# NewDoor.net
KiCad netlist of a schematic drawn in EAGLE
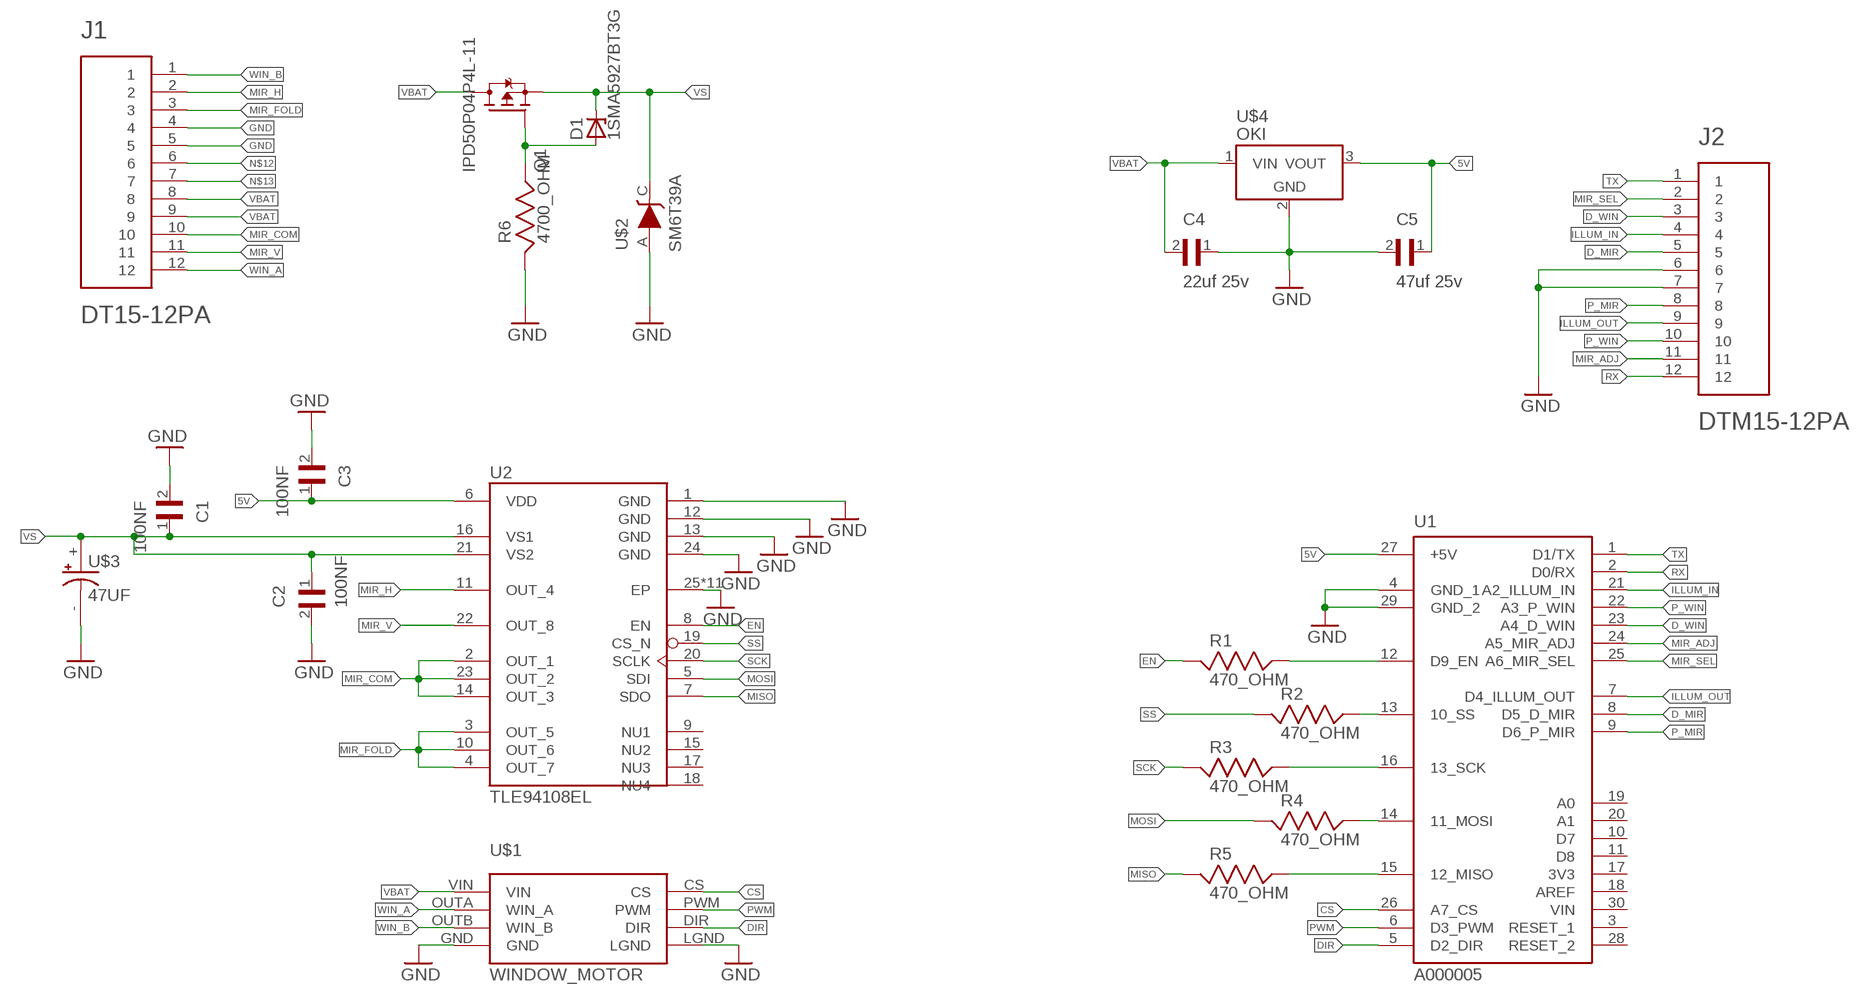
[diagram p0: schematic, sheet 1]

(export (version "E")
  (design (tool "Eeschema 10.0.6"))
  (components
    (comp (ref "C1")
      (value "100NF")
      (footprint "eagle-import:CAPC3216X110N")
      (fields (field (name "MF") "KEMET") (field (name "MP") "C1206C104J5RACTU"))
      (libsource (lib "eagle-import") (part "100NF"))
    )
    (comp (ref "C2")
      (value "100NF")
      (footprint "eagle-import:CAPC3216X110N")
      (fields (field (name "MF") "KEMET") (field (name "MP") "C1206C104J5RACTU"))
      (libsource (lib "eagle-import") (part "100NF"))
    )
    (comp (ref "C3")
      (value "100NF")
      (footprint "eagle-import:CAPC3216X110N")
      (fields (field (name "MF") "KEMET") (field (name "MP") "C1206C104J5RACTU"))
      (libsource (lib "eagle-import") (part "100NF"))
    )
    (comp (ref "C4")
      (value "22uf 25v")
      (footprint "eagle-import:CAP3216X125N")
      (fields (field (name "MF") "Murata Electronics") (field (name "MP") "GRM31CC81E226KE11L"))
      (libsource (lib "eagle-import") (part "GRM31CC81E226KE11L"))
    )
    (comp (ref "C5")
      (value "47uf 25v")
      (footprint "eagle-import:CAP3216X125N")
      (fields (field (name "MF") "Murata Electronics") (field (name "MP") "GRM31CC81E226KE11L"))
      (libsource (lib "eagle-import") (part "GRM31CC81E226KE11L"))
    )
    (comp (ref "D1")
      (value "1SMA5927BT3G")
      (footprint "eagle-import:DO214AC")
      (fields (field (name "MF") "ON Semiconductor"))
      (libsource (lib "eagle-import") (part "1SMA59BT3G27"))
    )
    (comp (ref "J1")
      (value "DT15-12PA")
      (footprint "eagle-import:TE_DT15-12PA")
      (fields (field (name "MF") "TE Connectivity"))
      (libsource (lib "eagle-import") (part "DT15-12PA"))
    )
    (comp (ref "J2")
      (value "DTM15-12PA")
      (footprint "eagle-import:TE_DTM15-12PA")
      (fields (field (name "MF") "TE Connectivity") (field (name "MPN") "DTM15-12PA "))
      (libsource (lib "eagle-import") (part "DTM15-12PA"))
    )
    (comp (ref "Q1")
      (value "IPD50P04P4L-11")
      (footprint "eagle-import:DPAK228P998X235-3N")
      (fields (field (name "MF") "Infineon Technologies"))
      (libsource (lib "eagle-import") (part "IPD50P04P4L-11"))
    )
    (comp (ref "R1")
      (value "470_OHM")
      (footprint "eagle-import:RESC3216X65")
      (fields (field (name "MF") "Yageo") (field (name "MP") "RC1206FR-13470RL"))
      (libsource (lib "eagle-import") (part "470_OHM"))
    )
    (comp (ref "R2")
      (value "470_OHM")
      (footprint "eagle-import:RESC3216X65")
      (fields (field (name "MF") "Yageo") (field (name "MP") "RC1206FR-13470RL"))
      (libsource (lib "eagle-import") (part "470_OHM"))
    )
    (comp (ref "R3")
      (value "470_OHM")
      (footprint "eagle-import:RESC3216X65")
      (fields (field (name "MF") "Yageo") (field (name "MP") "RC1206FR-13470RL"))
      (libsource (lib "eagle-import") (part "470_OHM"))
    )
    (comp (ref "R4")
      (value "470_OHM")
      (footprint "eagle-import:RESC3216X65")
      (fields (field (name "MF") "Yageo") (field (name "MP") "RC1206FR-13470RL"))
      (libsource (lib "eagle-import") (part "470_OHM"))
    )
    (comp (ref "R5")
      (value "470_OHM")
      (footprint "eagle-import:RESC3216X65")
      (fields (field (name "MF") "Yageo") (field (name "MP") "RC1206FR-13470RL"))
      (libsource (lib "eagle-import") (part "470_OHM"))
    )
    (comp (ref "R6")
      (value "4700_OHM")
      (footprint "eagle-import:RESC3216X70")
      (fields (field (name "MF") "Panasonic Electronic") (field (name "MP") "ERJ-8ENF4701V"))
      (libsource (lib "eagle-import") (part "4700_OHM"))
    )
    (comp (ref "U$1")
      (value "WINDOW_MOTOR")
      (footprint "eagle-import:POLOLU")
      (libsource (lib "eagle-import") (part "WINDOW_MOTOR"))
    )
    (comp (ref "U$2")
      (value "SM6T39A")
      (footprint "eagle-import:SM6T39A")
      (libsource (lib "eagle-import") (part "SM6T39A"))
    )
    (comp (ref "U$3")
      (value "47UF")
      (footprint "eagle-import:CAPAE1030X1200")
      (fields (field (name "MF") "Panasonic") (field (name "MP") "EEE-FC1C471AP"))
      (libsource (lib "eagle-import") (part "47UF"))
    )
    (comp (ref "U$4")
      (value "OKI")
      (footprint "eagle-import:OKI-78SR-H")
      (libsource (lib "eagle-import") (part "OKI"))
    )
    (comp (ref "U1")
      (value "A000005")
      (footprint "eagle-import:ARDUINO_A000005")
      (fields (field (name "MF") "Arduino"))
      (libsource (lib "eagle-import") (part "A000005"))
    )
    (comp (ref "U2")
      (value "TLE94108EL")
      (footprint "eagle-import:SOP65P600X170-25N")
      (libsource (lib "eagle-import") (part "TLE94108EL"))
    )
  )
  (nets
    (net (code "1") (name "5V") (class "Default")
      (node (ref "C3") (pin "1") (pinfunction "1_1") (pintype "passive"))
      (node (ref "C5") (pin "1") (pinfunction "1_1") (pintype "passive"))
      (node (ref "U$4") (pin "3") (pinfunction "VOUT_3") (pintype "power_in"))
      (node (ref "U1") (pin "27") (pinfunction "+5V_27") (pintype "power_in"))
      (node (ref "U2") (pin "6") (pinfunction "VDD_6") (pintype "power_in"))
    )
    (net (code "2") (name "CS") (class "Default")
      (node (ref "U$1") (pin "CS") (pinfunction "CS_CS") (pintype "output"))
      (node (ref "U1") (pin "26") (pinfunction "A7_CS_26") (pintype "input"))
    )
    (net (code "3") (name "DIR") (class "Default")
      (node (ref "U$1") (pin "DIR") (pinfunction "DIR_DIR") (pintype "input"))
      (node (ref "U1") (pin "5") (pinfunction "D2_DIR_5") (pintype "output"))
    )
    (net (code "4") (name "D_MIR") (class "Default")
      (node (ref "J2") (pin "5") (pinfunction "5_5") (pintype "passive"))
      (node (ref "U1") (pin "8") (pinfunction "D5_D_MIR_8") (pintype "output"))
    )
    (net (code "5") (name "D_WIN") (class "Default")
      (node (ref "J2") (pin "3") (pinfunction "3_3") (pintype "passive"))
      (node (ref "U1") (pin "23") (pinfunction "A4_D_WIN_23") (pintype "input"))
    )
    (net (code "6") (name "EN") (class "Default")
      (node (ref "R1") (pin "1") (pinfunction "1_1") (pintype "passive"))
      (node (ref "U2") (pin "8") (pinfunction "EN_8") (pintype "input"))
    )
    (net (code "7") (name "GND") (class "Default")
      (node (ref "C1") (pin "2") (pinfunction "2_2") (pintype "passive"))
      (node (ref "C2") (pin "2") (pinfunction "2_2") (pintype "passive"))
      (node (ref "C3") (pin "2") (pinfunction "2_2") (pintype "passive"))
      (node (ref "C4") (pin "1") (pinfunction "1_1") (pintype "passive"))
      (node (ref "C5") (pin "2") (pinfunction "2_2") (pintype "passive"))
      (node (ref "J1") (pin "4") (pinfunction "4_4") (pintype "passive"))
      (node (ref "J1") (pin "5") (pinfunction "5_5") (pintype "passive"))
      (node (ref "J2") (pin "6") (pinfunction "6_6") (pintype "passive"))
      (node (ref "J2") (pin "7") (pinfunction "7_7") (pintype "passive"))
      (node (ref "R6") (pin "1") (pinfunction "1_1") (pintype "passive"))
      (node (ref "U$1") (pin "GND") (pinfunction "GND_GND") (pintype "power_in"))
      (node (ref "U$1") (pin "LGND") (pinfunction "LGND_LGND") (pintype "power_in"))
      (node (ref "U$2") (pin "A") (pinfunction "A_A") (pintype "passive"))
      (node (ref "U$3") (pin "-") (pinfunction "-_-") (pintype "passive"))
      (node (ref "U$4") (pin "2") (pinfunction "GND_2") (pintype "power_in"))
      (node (ref "U1") (pin "29") (pinfunction "GND_2_29") (pintype "power_in"))
      (node (ref "U1") (pin "4") (pinfunction "GND_1_4") (pintype "power_in"))
      (node (ref "U2") (pin "1") (pinfunction "GND_1") (pintype "power_in"))
      (node (ref "U2") (pin "12") (pinfunction "GND_12") (pintype "power_in"))
      (node (ref "U2") (pin "13") (pinfunction "GND_13") (pintype "power_in"))
      (node (ref "U2") (pin "24") (pinfunction "GND_24") (pintype "power_in"))
      (node (ref "U2") (pin "25") (pinfunction "EP_25") (pintype "power_in"))
      (node (ref "U2") (pin "GND") (pinfunction "EP_GND") (pintype "power_in"))
      (node (ref "U2") (pin "GND1") (pinfunction "EP_GND1") (pintype "power_in"))
      (node (ref "U2") (pin "GND2") (pinfunction "EP_GND2") (pintype "power_in"))
      (node (ref "U2") (pin "GND3") (pinfunction "EP_GND3") (pintype "power_in"))
      (node (ref "U2") (pin "GND4") (pinfunction "EP_GND4") (pintype "power_in"))
      (node (ref "U2") (pin "GND5") (pinfunction "EP_GND5") (pintype "power_in"))
      (node (ref "U2") (pin "GND6") (pinfunction "EP_GND6") (pintype "power_in"))
      (node (ref "U2") (pin "GND7") (pinfunction "EP_GND7") (pintype "power_in"))
      (node (ref "U2") (pin "GND8") (pinfunction "EP_GND8") (pintype "power_in"))
      (node (ref "U2") (pin "GND9") (pinfunction "EP_GND9") (pintype "power_in"))
    )
    (net (code "8") (name "ILLUM_IN") (class "Default")
      (node (ref "J2") (pin "4") (pinfunction "4_4") (pintype "passive"))
      (node (ref "U1") (pin "21") (pinfunction "A2_ILLUM_IN_21") (pintype "passive"))
    )
    (net (code "9") (name "ILLUM_OUT") (class "Default")
      (node (ref "J2") (pin "9") (pinfunction "9_9") (pintype "passive"))
      (node (ref "U1") (pin "7") (pinfunction "D4_ILLUM_OUT_7") (pintype "output"))
    )
    (net (code "10") (name "MIR_ADJ") (class "Default")
      (node (ref "J2") (pin "11") (pinfunction "11_11") (pintype "passive"))
      (node (ref "U1") (pin "24") (pinfunction "A5_MIR_ADJ_24") (pintype "input"))
    )
    (net (code "11") (name "MIR_COM") (class "Default")
      (node (ref "J1") (pin "10") (pinfunction "10_10") (pintype "passive"))
      (node (ref "U2") (pin "14") (pinfunction "OUT_3_14") (pintype "bidirectional"))
      (node (ref "U2") (pin "2") (pinfunction "OUT_1_2") (pintype "bidirectional"))
      (node (ref "U2") (pin "23") (pinfunction "OUT_2_23") (pintype "bidirectional"))
    )
    (net (code "12") (name "MIR_FOLD") (class "Default")
      (node (ref "J1") (pin "3") (pinfunction "3_3") (pintype "passive"))
      (node (ref "U2") (pin "10") (pinfunction "OUT_6_10") (pintype "bidirectional"))
      (node (ref "U2") (pin "3") (pinfunction "OUT_5_3") (pintype "bidirectional"))
      (node (ref "U2") (pin "4") (pinfunction "OUT_7_4") (pintype "bidirectional"))
    )
    (net (code "13") (name "MIR_H") (class "Default")
      (node (ref "J1") (pin "2") (pinfunction "2_2") (pintype "passive"))
      (node (ref "U2") (pin "11") (pinfunction "OUT_4_11") (pintype "bidirectional"))
    )
    (net (code "14") (name "MIR_SEL") (class "Default")
      (node (ref "J2") (pin "2") (pinfunction "2_2") (pintype "passive"))
      (node (ref "U1") (pin "25") (pinfunction "A6_MIR_SEL_25") (pintype "input"))
    )
    (net (code "15") (name "MIR_V") (class "Default")
      (node (ref "J1") (pin "11") (pinfunction "11_11") (pintype "passive"))
      (node (ref "U2") (pin "22") (pinfunction "OUT_8_22") (pintype "bidirectional"))
    )
    (net (code "16") (name "MISO") (class "Default")
      (node (ref "R5") (pin "1") (pinfunction "1_1") (pintype "passive"))
      (node (ref "U2") (pin "7") (pinfunction "SDO_7") (pintype "output"))
    )
    (net (code "17") (name "MOSI") (class "Default")
      (node (ref "R4") (pin "1") (pinfunction "1_1") (pintype "passive"))
      (node (ref "U2") (pin "5") (pinfunction "SDI_5") (pintype "input"))
    )
    (net (code "18") (name "N$12") (class "Default")
      (node (ref "J1") (pin "6") (pinfunction "6_6") (pintype "passive"))
    )
    (net (code "19") (name "N$13") (class "Default")
      (node (ref "J1") (pin "7") (pinfunction "7_7") (pintype "passive"))
    )
    (net (code "20") (name "Net-(Q1-G)") (class "Default")
      (node (ref "D1") (pin "A") (pinfunction "A_A") (pintype "passive"))
      (node (ref "Q1") (pin "1") (pinfunction "G_1") (pintype "passive"))
      (node (ref "R6") (pin "2") (pinfunction "2_2") (pintype "passive"))
    )
    (net (code "21") (name "Net-(U1-10_SS)") (class "Default")
      (node (ref "R2") (pin "2") (pinfunction "2_2") (pintype "passive"))
      (node (ref "U1") (pin "13") (pinfunction "10_SS_13") (pintype "output"))
    )
    (net (code "22") (name "Net-(U1-11_MOSI)") (class "Default")
      (node (ref "R4") (pin "2") (pinfunction "2_2") (pintype "passive"))
      (node (ref "U1") (pin "14") (pinfunction "11_MOSI_14") (pintype "output"))
    )
    (net (code "23") (name "Net-(U1-12_MISO)") (class "Default")
      (node (ref "R5") (pin "2") (pinfunction "2_2") (pintype "passive"))
      (node (ref "U1") (pin "15") (pinfunction "12_MISO_15") (pintype "input"))
    )
    (net (code "24") (name "Net-(U1-13_SCK)") (class "Default")
      (node (ref "R3") (pin "2") (pinfunction "2_2") (pintype "passive"))
      (node (ref "U1") (pin "16") (pinfunction "13_SCK_16") (pintype "output"))
    )
    (net (code "25") (name "Net-(U1-D9_EN)") (class "Default")
      (node (ref "R1") (pin "2") (pinfunction "2_2") (pintype "passive"))
      (node (ref "U1") (pin "12") (pinfunction "D9_EN_12") (pintype "output"))
    )
    (net (code "26") (name "PWM") (class "Default")
      (node (ref "U$1") (pin "PWM") (pinfunction "PWM_PWM") (pintype "input"))
      (node (ref "U1") (pin "6") (pinfunction "D3_PWM_6") (pintype "output"))
    )
    (net (code "27") (name "P_MIR") (class "Default")
      (node (ref "J2") (pin "8") (pinfunction "8_8") (pintype "passive"))
      (node (ref "U1") (pin "9") (pinfunction "D6_P_MIR_9") (pintype "output"))
    )
    (net (code "28") (name "P_WIN") (class "Default")
      (node (ref "J2") (pin "10") (pinfunction "10_10") (pintype "passive"))
      (node (ref "U1") (pin "22") (pinfunction "A3_P_WIN_22") (pintype "input"))
    )
    (net (code "29") (name "RX") (class "Default")
      (node (ref "J2") (pin "12") (pinfunction "12_12") (pintype "passive"))
      (node (ref "U1") (pin "2") (pinfunction "D0/RX_2") (pintype "input"))
    )
    (net (code "30") (name "SCK") (class "Default")
      (node (ref "R3") (pin "1") (pinfunction "1_1") (pintype "passive"))
      (node (ref "U2") (pin "20") (pinfunction "SCLK_20") (pintype "input"))
    )
    (net (code "31") (name "SS") (class "Default")
      (node (ref "R2") (pin "1") (pinfunction "1_1") (pintype "passive"))
      (node (ref "U2") (pin "19") (pinfunction "CS_N_19") (pintype "input"))
    )
    (net (code "32") (name "TX") (class "Default")
      (node (ref "J2") (pin "1") (pinfunction "1_1") (pintype "passive"))
      (node (ref "U1") (pin "1") (pinfunction "D1/TX_1") (pintype "output"))
    )
    (net (code "33") (name "VBAT") (class "Default")
      (node (ref "C4") (pin "2") (pinfunction "2_2") (pintype "passive"))
      (node (ref "J1") (pin "8") (pinfunction "8_8") (pintype "passive"))
      (node (ref "J1") (pin "9") (pinfunction "9_9") (pintype "passive"))
      (node (ref "Q1") (pin "2") (pinfunction "D_2") (pintype "passive"))
      (node (ref "U$1") (pin "VIN") (pinfunction "VIN_VIN") (pintype "power_in"))
      (node (ref "U$4") (pin "1") (pinfunction "VIN_1") (pintype "power_in"))
    )
    (net (code "34") (name "VS") (class "Default")
      (node (ref "C1") (pin "1") (pinfunction "1_1") (pintype "passive"))
      (node (ref "C2") (pin "1") (pinfunction "1_1") (pintype "passive"))
      (node (ref "D1") (pin "C") (pinfunction "C_C") (pintype "passive"))
      (node (ref "Q1") (pin "3") (pinfunction "S_3") (pintype "passive"))
      (node (ref "U$2") (pin "C") (pinfunction "C_C") (pintype "passive"))
      (node (ref "U$3") (pin "+") (pinfunction "+_+") (pintype "passive"))
      (node (ref "U2") (pin "16") (pinfunction "VS1_16") (pintype "power_in"))
      (node (ref "U2") (pin "21") (pinfunction "VS2_21") (pintype "power_in"))
    )
    (net (code "35") (name "WIN_A") (class "Default")
      (node (ref "J1") (pin "12") (pinfunction "12_12") (pintype "passive"))
      (node (ref "U$1") (pin "OUTA") (pinfunction "WIN_A_OUTA") (pintype "output"))
    )
    (net (code "36") (name "WIN_B") (class "Default")
      (node (ref "J1") (pin "1") (pinfunction "1_1") (pintype "passive"))
      (node (ref "U$1") (pin "OUTB") (pinfunction "WIN_B_OUTB") (pintype "output"))
    )
    (net (code "37") (name "unconnected-(U1-3V3-Pad17)") (class "Default")
      (node (ref "U1") (pin "17") (pinfunction "3V3_17") (pintype "passive"))
    )
    (net (code "38") (name "unconnected-(U1-A0-Pad19)") (class "Default")
      (node (ref "U1") (pin "19") (pinfunction "A0_19") (pintype "passive"))
    )
    (net (code "39") (name "unconnected-(U1-A1-Pad20)") (class "Default")
      (node (ref "U1") (pin "20") (pinfunction "A1_20") (pintype "passive"))
    )
    (net (code "40") (name "unconnected-(U1-AREF-Pad18)") (class "Default")
      (node (ref "U1") (pin "18") (pinfunction "AREF_18") (pintype "passive"))
    )
    (net (code "41") (name "unconnected-(U1-D7-Pad10)") (class "Default")
      (node (ref "U1") (pin "10") (pinfunction "D7_10") (pintype "output"))
    )
    (net (code "42") (name "unconnected-(U1-D8-Pad11)") (class "Default")
      (node (ref "U1") (pin "11") (pinfunction "D8_11") (pintype "passive"))
    )
    (net (code "43") (name "unconnected-(U1-RESET_1-Pad3)") (class "Default")
      (node (ref "U1") (pin "3") (pinfunction "RESET_1_3") (pintype "passive"))
    )
    (net (code "44") (name "unconnected-(U1-RESET_2-Pad28)") (class "Default")
      (node (ref "U1") (pin "28") (pinfunction "RESET_2_28") (pintype "passive"))
    )
    (net (code "45") (name "unconnected-(U1-VIN-Pad30)") (class "Default")
      (node (ref "U1") (pin "30") (pinfunction "VIN_30") (pintype "passive"))
    )
    (net (code "46") (name "unconnected-(U2-NU1-Pad9)") (class "Default")
      (node (ref "U2") (pin "9") (pinfunction "NU1_9") (pintype "passive"))
    )
    (net (code "47") (name "unconnected-(U2-NU2-Pad15)") (class "Default")
      (node (ref "U2") (pin "15") (pinfunction "NU2_15") (pintype "passive"))
    )
    (net (code "48") (name "unconnected-(U2-NU3-Pad17)") (class "Default")
      (node (ref "U2") (pin "17") (pinfunction "NU3_17") (pintype "passive"))
    )
    (net (code "49") (name "unconnected-(U2-NU4-Pad18)") (class "Default")
      (node (ref "U2") (pin "18") (pinfunction "NU4_18") (pintype "passive"))
    )
  )
)
